# 8-Other_Inputs.net
KiCad netlist of a schematic drawn in Altium Designer
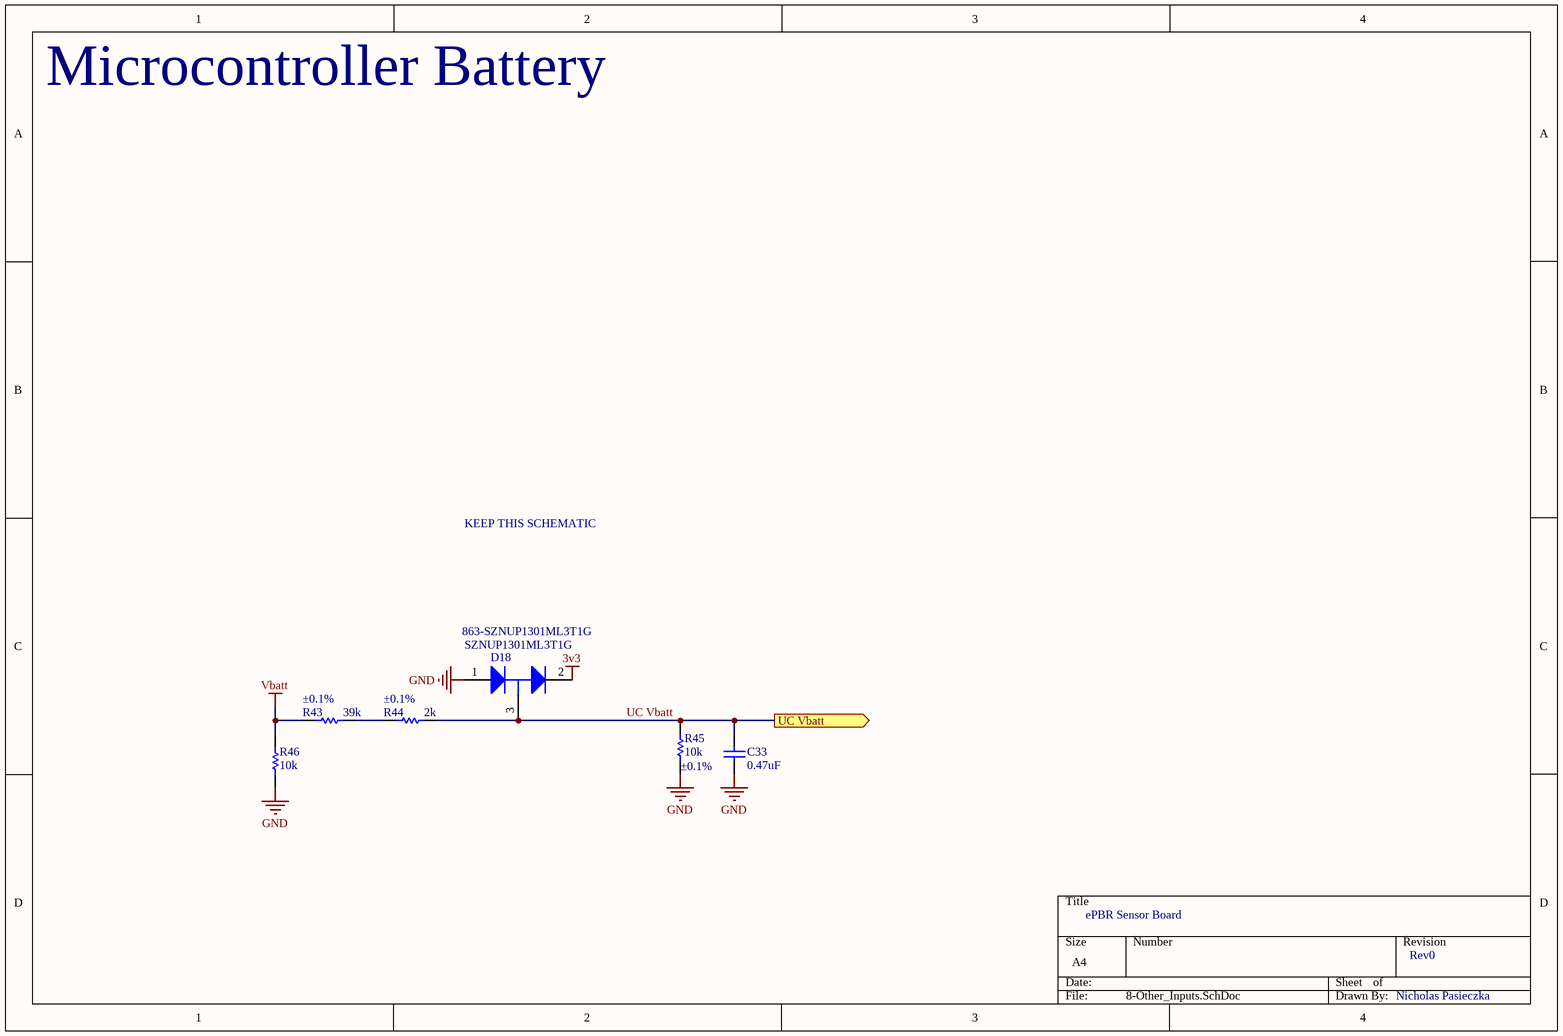
[diagram p0: 8-Other_Inputs.SchDoc]

(export (version "E")
  (design (tool "Eeschema 10.0.6"))
  (components
    (comp (ref "C33")
      (value "0.47uF")
      (footprint "1608[0603]")
      (description "Capacitor")
      (fields
        (field (name "MANUFACTURER") "Yageo")
        (field (name "MANUFACTURER PART NUMBER") "CC0603KRX7R8BB474")
      )
      (libsource (lib "Miscellaneous Devices") (part "Cap"))
    )
    (comp (ref "D18")
      (value "SZNUP1301ML3T1G")
      (footprint "ONSC-SOT-23-3-318-08_V")
      (fields
        (field (name "MANUFACTURER") "On Semiconductor")
        (field (name "SUPPLIER PART NUMBER 1") "863-SZNUP1301ML3T1G")
      )
      (libsource (lib "Altium Content Vault") (part "ONSC-NUP1301-SOT-23-3-318-08"))
    )
    (comp (ref "R43")
      (value "39k")
      (footprint "1608[0603]")
      (description "Resistor")
      (fields
        (field (name "MANUFACTURER") "Yageo")
        (field (name "MANUFACTURER PART NUMBER") "RT0603BRD0739KL")
        (field (name "TOLERANCE") "±0.1%")
      )
      (libsource (lib "Miscellaneous Devices") (part "Res1"))
    )
    (comp (ref "R44")
      (value "2k")
      (footprint "1608[0603]")
      (description "Resistor")
      (fields
        (field (name "MANUFACTURER") "Yageo")
        (field (name "MANUFACTURER PART NUMBER") "AT0603BRD072KL")
        (field (name "TOLERANCE") "±0.1%")
      )
      (libsource (lib "Miscellaneous Devices") (part "Res1"))
    )
    (comp (ref "R45")
      (value "10k")
      (footprint "1608[0603]")
      (description "Resistor")
      (fields
        (field (name "MANUFACTURER") "Yageo")
        (field (name "MANUFACTURER PART NUMBER") "RT0603BRD0710KL")
        (field (name "TOLERANCE") "±0.1%")
      )
      (libsource (lib "Miscellaneous Devices") (part "Res1"))
    )
    (comp (ref "R46")
      (value "10k")
      (footprint "1608[0603]")
      (description "Resistor")
      (fields
        (field (name "MANUFACTURER") "Yageo")
        (field (name "MANUFACTURER PART NUMBER") "RC0603JR-0710KL")
      )
      (libsource (lib "Miscellaneous Devices") (part "Res1"))
    )
  )
  (nets
    (net (code "1") (name "/UC Vbatt") (class "Default")
      (node (ref "C33") (pin "2") (pinfunction "2_2") (pintype "passive"))
      (node (ref "D18") (pin "3") (pinfunction "K/A_3") (pintype "passive"))
      (node (ref "R44") (pin "2") (pinfunction "2_2") (pintype "passive"))
      (node (ref "R45") (pin "2") (pinfunction "2_2") (pintype "passive"))
    )
    (net (code "2") (name "3v3") (class "Default")
      (node (ref "D18") (pin "2") (pinfunction "K_2") (pintype "passive"))
    )
    (net (code "3") (name "GND") (class "Default")
      (node (ref "C33") (pin "1") (pinfunction "1_1") (pintype "passive"))
      (node (ref "D18") (pin "1") (pinfunction "A_1") (pintype "passive"))
      (node (ref "R45") (pin "1") (pinfunction "1_1") (pintype "passive"))
      (node (ref "R46") (pin "1") (pinfunction "1_1") (pintype "passive"))
    )
    (net (code "4") (name "Net-(R43-Pad2)") (class "Default")
      (node (ref "R43") (pin "2") (pinfunction "2_2") (pintype "passive"))
      (node (ref "R44") (pin "1") (pinfunction "1_1") (pintype "passive"))
    )
    (net (code "5") (name "Vbatt") (class "Default")
      (node (ref "R43") (pin "1") (pinfunction "1_1") (pintype "passive"))
      (node (ref "R46") (pin "2") (pinfunction "2_2") (pintype "passive"))
    )
  )
)
